# GECBalloonMCUFlightBoard_REV2_1_7-19-19.net
KiCad netlist of a schematic drawn in EAGLE
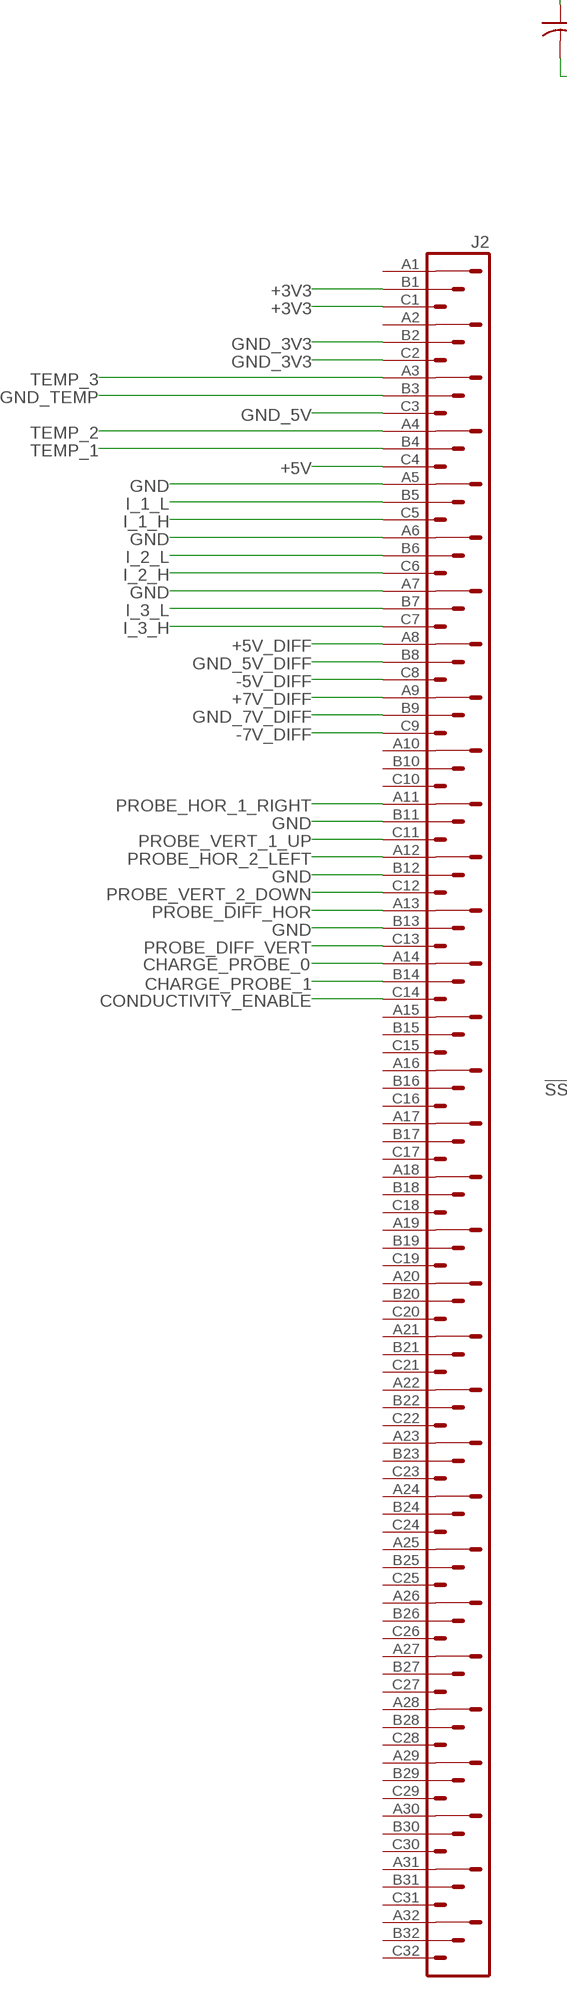
[diagram p0: schematic, sheet 1, part 1 of 2]
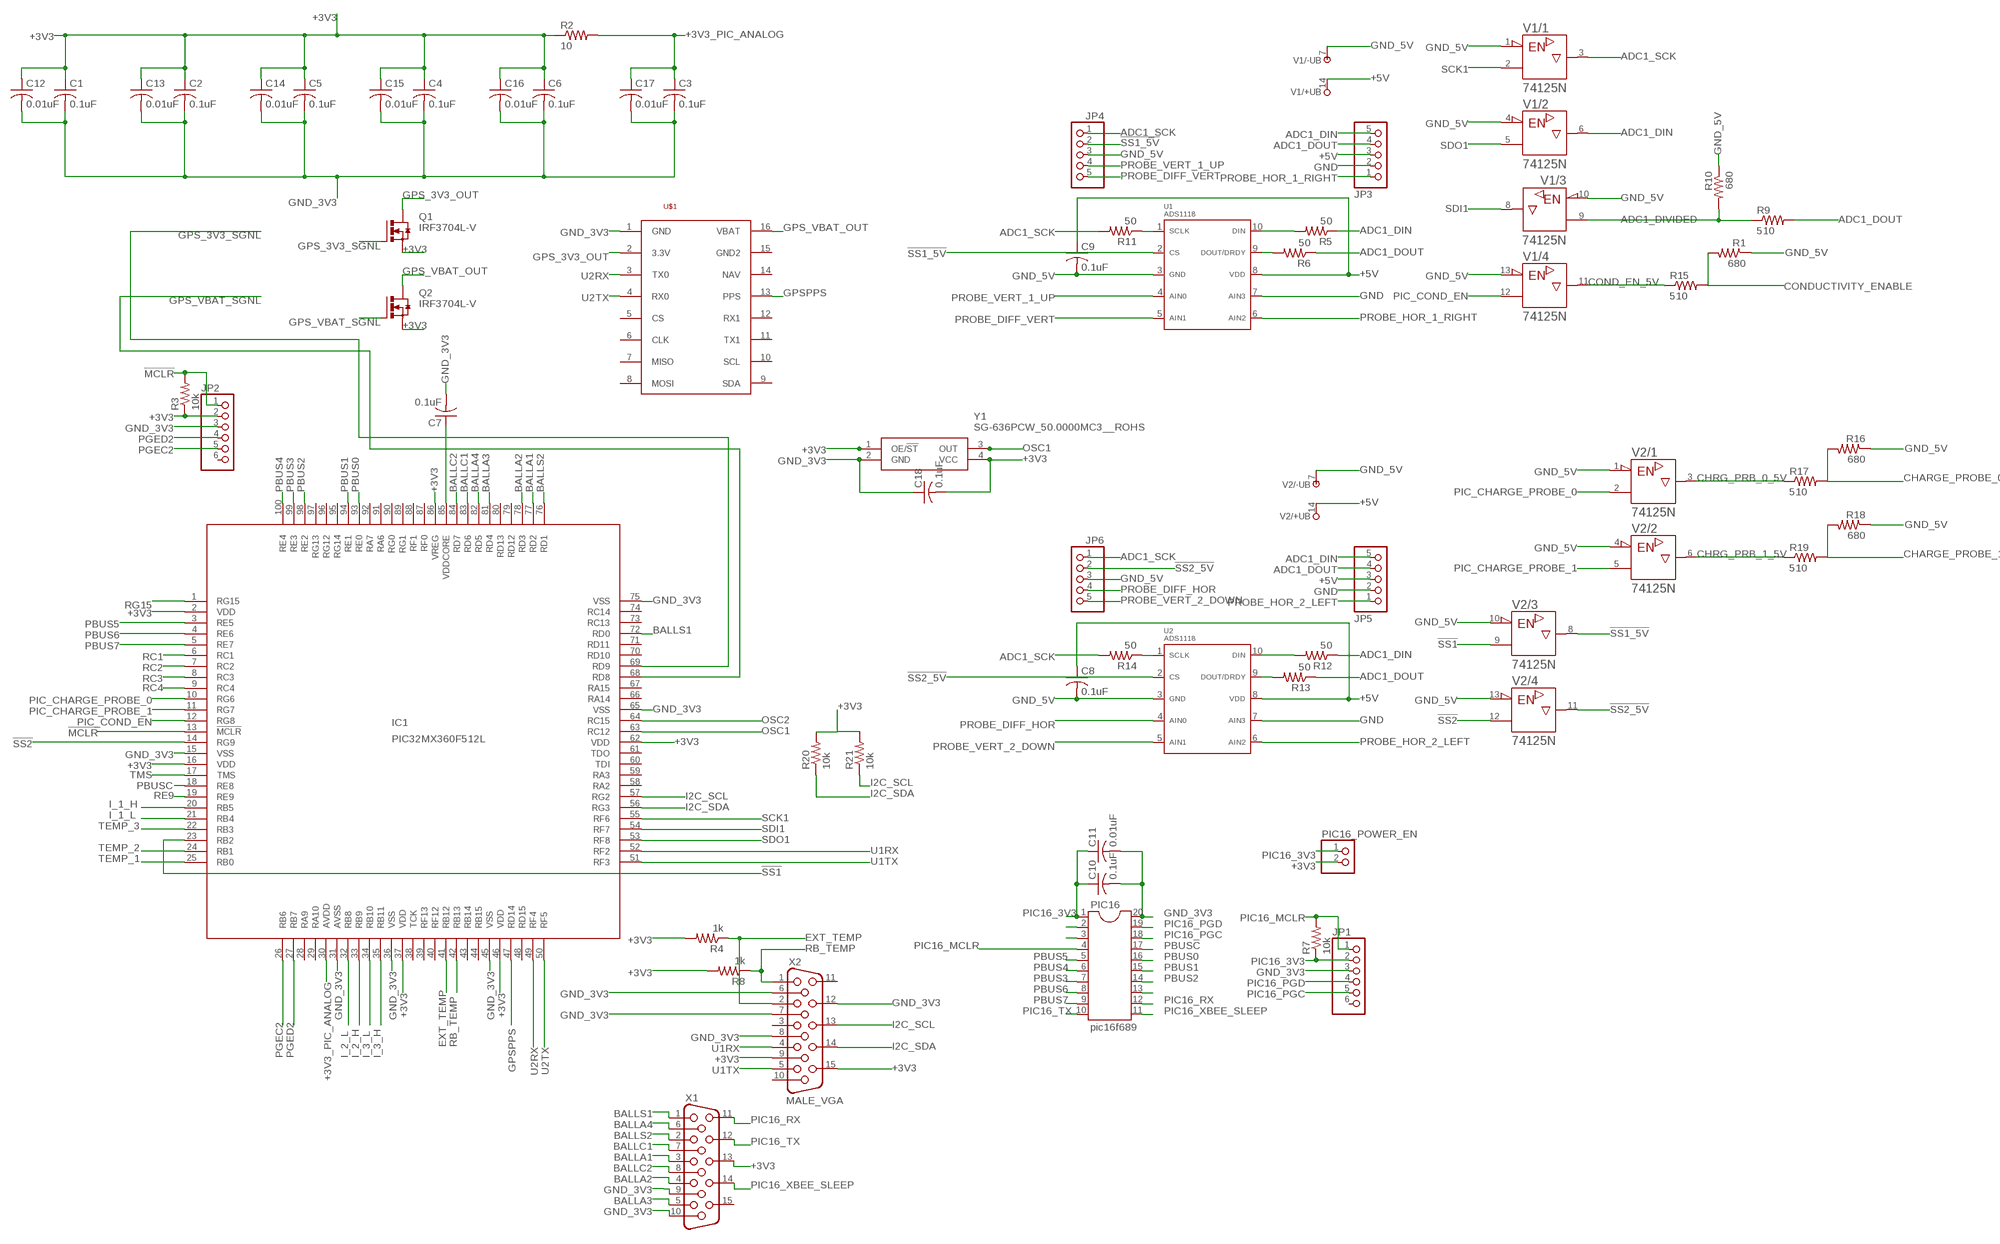
[diagram p1: schematic, sheet 1, part 2 of 2]

(export (version "E")
  (design (tool "Eeschema 10.0.6"))
  (components
    (comp (ref "C1")
      (value "0.1uF")
      (footprint "eagle-import:C1206")
      (libsource (lib "eagle-import") (part "C-USC1206"))
    )
    (comp (ref "C2")
      (value "0.1uF")
      (footprint "eagle-import:C1206")
      (libsource (lib "eagle-import") (part "C-USC1206"))
    )
    (comp (ref "C3")
      (value "0.1uF")
      (footprint "eagle-import:C1206")
      (libsource (lib "eagle-import") (part "C-USC1206"))
    )
    (comp (ref "C4")
      (value "0.1uF")
      (footprint "eagle-import:C1206")
      (libsource (lib "eagle-import") (part "C-USC1206"))
    )
    (comp (ref "C5")
      (value "0.1uF")
      (footprint "eagle-import:C1206")
      (libsource (lib "eagle-import") (part "C-USC1206"))
    )
    (comp (ref "C6")
      (value "0.1uF")
      (footprint "eagle-import:C1206")
      (libsource (lib "eagle-import") (part "C-USC1206"))
    )
    (comp (ref "C7")
      (value "0.1uF")
      (footprint "eagle-import:C1206")
      (libsource (lib "eagle-import") (part "C-USC1206"))
    )
    (comp (ref "C8")
      (value "0.1uF")
      (footprint "eagle-import:C1206")
      (libsource (lib "eagle-import") (part "C-USC1206"))
    )
    (comp (ref "C9")
      (value "0.1uF")
      (footprint "eagle-import:C1206")
      (libsource (lib "eagle-import") (part "C-USC1206"))
    )
    (comp (ref "C10")
      (value "0.1uF")
      (footprint "eagle-import:C1206")
      (libsource (lib "eagle-import") (part "C-USC1206"))
    )
    (comp (ref "C11")
      (value "0.01uF")
      (footprint "eagle-import:C1206")
      (libsource (lib "eagle-import") (part "C-USC1206"))
    )
    (comp (ref "C12")
      (value "0.01uF")
      (footprint "eagle-import:C1206")
      (libsource (lib "eagle-import") (part "C-USC1206"))
    )
    (comp (ref "C13")
      (value "0.01uF")
      (footprint "eagle-import:C1206")
      (libsource (lib "eagle-import") (part "C-USC1206"))
    )
    (comp (ref "C14")
      (value "0.01uF")
      (footprint "eagle-import:C1206")
      (libsource (lib "eagle-import") (part "C-USC1206"))
    )
    (comp (ref "C15")
      (value "0.01uF")
      (footprint "eagle-import:C1206")
      (libsource (lib "eagle-import") (part "C-USC1206"))
    )
    (comp (ref "C16")
      (value "0.01uF")
      (footprint "eagle-import:C1206")
      (libsource (lib "eagle-import") (part "C-USC1206"))
    )
    (comp (ref "C17")
      (value "0.01uF")
      (footprint "eagle-import:C1206")
      (libsource (lib "eagle-import") (part "C-USC1206"))
    )
    (comp (ref "C18")
      (value "0.1uF")
      (footprint "eagle-import:C1206")
      (libsource (lib "eagle-import") (part "C-USC1206"))
    )
    (comp (ref "IC1")
      (value "PIC32MX360F512L")
      (footprint "eagle-import:TQFP100")
      (libsource (lib "eagle-import") (part "PIC32MX360F512L"))
    )
    (comp (ref "J2")
      (value "VG96KB")
      (footprint "eagle-import:VG96KB")
      (libsource (lib "eagle-import") (part "VG96KB"))
    )
    (comp (ref "JP1")
      (value "PINHD-1X6")
      (footprint "eagle-import:1X06")
      (libsource (lib "eagle-import") (part "PINHD-1X6"))
    )
    (comp (ref "JP2")
      (value "PINHD-1X6")
      (footprint "eagle-import:1X06")
      (libsource (lib "eagle-import") (part "PINHD-1X6"))
    )
    (comp (ref "JP3")
      (value "PINHD-1X5")
      (footprint "eagle-import:1X05")
      (libsource (lib "eagle-import") (part "PINHD-1X5"))
    )
    (comp (ref "JP4")
      (value "PINHD-1X5")
      (footprint "eagle-import:1X05")
      (libsource (lib "eagle-import") (part "PINHD-1X5"))
    )
    (comp (ref "JP5")
      (value "PINHD-1X5")
      (footprint "eagle-import:1X05")
      (libsource (lib "eagle-import") (part "PINHD-1X5"))
    )
    (comp (ref "JP6")
      (value "PINHD-1X5")
      (footprint "eagle-import:1X05")
      (libsource (lib "eagle-import") (part "PINHD-1X5"))
    )
    (comp (ref "PIC16")
      (value "pic16f689")
      (footprint "eagle-import:DIL20")
      (libsource (lib "eagle-import") (part "DIL20"))
    )
    (comp (ref "PIC16_POWER_EN")
      (value "PINHD-1X2")
      (footprint "eagle-import:1X02")
      (libsource (lib "eagle-import") (part "PINHD-1X2"))
    )
    (comp (ref "Q1")
      (value "IRF3704L-V")
      (footprint "eagle-import:TO262-V")
      (libsource (lib "eagle-import") (part "IRF3704L-V"))
    )
    (comp (ref "Q2")
      (value "IRF3704L-V")
      (footprint "eagle-import:TO262-V")
      (libsource (lib "eagle-import") (part "IRF3704L-V"))
    )
    (comp (ref "R1")
      (value "680")
      (footprint "eagle-import:R1206")
      (libsource (lib "eagle-import") (part "resistor_R-US_R1206"))
    )
    (comp (ref "R2")
      (value "10")
      (footprint "eagle-import:M1206")
      (libsource (lib "eagle-import") (part "R-US_M1206"))
    )
    (comp (ref "R3")
      (value "10k")
      (footprint "eagle-import:M1206")
      (libsource (lib "eagle-import") (part "R-US_M1206"))
    )
    (comp (ref "R4")
      (value "1k")
      (footprint "eagle-import:0414_15")
      (libsource (lib "eagle-import") (part "resistor_R-US_0414/15"))
    )
    (comp (ref "R5")
      (value "50")
      (footprint "eagle-import:M1206")
      (libsource (lib "eagle-import") (part "R-US_M1206"))
    )
    (comp (ref "R6")
      (value "50")
      (footprint "eagle-import:M1206")
      (libsource (lib "eagle-import") (part "R-US_M1206"))
    )
    (comp (ref "R7")
      (value "10k")
      (footprint "eagle-import:M1206")
      (libsource (lib "eagle-import") (part "R-US_M1206"))
    )
    (comp (ref "R8")
      (value "1k")
      (footprint "eagle-import:0414_15")
      (libsource (lib "eagle-import") (part "resistor_R-US_0414/15"))
    )
    (comp (ref "R9")
      (value "510")
      (footprint "eagle-import:R1206")
      (libsource (lib "eagle-import") (part "resistor_R-US_R1206"))
    )
    (comp (ref "R10")
      (value "680")
      (footprint "eagle-import:R1206")
      (libsource (lib "eagle-import") (part "resistor_R-US_R1206"))
    )
    (comp (ref "R11")
      (value "50")
      (footprint "eagle-import:M1206")
      (libsource (lib "eagle-import") (part "R-US_M1206"))
    )
    (comp (ref "R12")
      (value "50")
      (footprint "eagle-import:M1206")
      (libsource (lib "eagle-import") (part "R-US_M1206"))
    )
    (comp (ref "R13")
      (value "50")
      (footprint "eagle-import:M1206")
      (libsource (lib "eagle-import") (part "R-US_M1206"))
    )
    (comp (ref "R14")
      (value "50")
      (footprint "eagle-import:M1206")
      (libsource (lib "eagle-import") (part "R-US_M1206"))
    )
    (comp (ref "R15")
      (value "510")
      (footprint "eagle-import:R1206")
      (libsource (lib "eagle-import") (part "resistor_R-US_R1206"))
    )
    (comp (ref "R16")
      (value "680")
      (footprint "eagle-import:R1206")
      (libsource (lib "eagle-import") (part "resistor_R-US_R1206"))
    )
    (comp (ref "R17")
      (value "510")
      (footprint "eagle-import:R1206")
      (libsource (lib "eagle-import") (part "resistor_R-US_R1206"))
    )
    (comp (ref "R18")
      (value "680")
      (footprint "eagle-import:R1206")
      (libsource (lib "eagle-import") (part "resistor_R-US_R1206"))
    )
    (comp (ref "R19")
      (value "510")
      (footprint "eagle-import:R1206")
      (libsource (lib "eagle-import") (part "resistor_R-US_R1206"))
    )
    (comp (ref "R20")
      (value "10k")
      (footprint "eagle-import:M1206")
      (libsource (lib "eagle-import") (part "R-US_M1206"))
    )
    (comp (ref "R21")
      (value "10k")
      (footprint "eagle-import:M1206")
      (libsource (lib "eagle-import") (part "R-US_M1206"))
    )
    (comp (ref "U$1")
      (value "SPARKFUN_VENUS_GPS_BREAKOUT")
      (footprint "eagle-import:SPARKFUN_BOARD")
      (libsource (lib "eagle-import") (part "SPARKFUN_VENUS_GPS_BREAKOUT"))
    )
    (comp (ref "U1")
      (value "ADS1118")
      (footprint "eagle-import:MSOP10")
      (libsource (lib "eagle-import") (part "ADS1118_MSOP10"))
    )
    (comp (ref "U2")
      (value "ADS1118")
      (footprint "eagle-import:MSOP10")
      (libsource (lib "eagle-import") (part "ADS1118_MSOP10"))
    )
    (comp (ref "V1")
      (value "74125N")
      (footprint "eagle-import:DIL14")
      (libsource (lib "eagle-import") (part "74125N"))
    )
    (comp (ref "V2")
      (value "74125N")
      (footprint "eagle-import:DIL14")
      (libsource (lib "eagle-import") (part "74125N"))
    )
    (comp (ref "X1")
      (value "HF15H")
      (footprint "eagle-import:HDF15H")
      (libsource (lib "eagle-import") (part "HF15H"))
    )
    (comp (ref "X2")
      (value "MALE_VGA")
      (footprint "eagle-import:MALE_PACKAGE")
      (libsource (lib "eagle-import") (part "MALE_VGA"))
    )
    (comp (ref "Y1")
      (value "SG-636PCW_50.0000MC3__ROHS")
      (footprint "eagle-import:SG-636")
      (fields (field (name "ARROW_PART_NUMBER") "SG-636PCW 50.0000MC3: ROHS"))
      (libsource (lib "eagle-import") (part "SG-636PCW_50.0000MC3__ROHS"))
    )
  )
  (nets
    (net (code "1") (name "/+3V3") (class "Default")
      (node (ref "C1") (pin "1") (pinfunction "1_1") (pintype "passive"))
      (node (ref "C12") (pin "1") (pinfunction "1_1") (pintype "passive"))
      (node (ref "C13") (pin "1") (pinfunction "1_1") (pintype "passive"))
      (node (ref "C14") (pin "1") (pinfunction "1_1") (pintype "passive"))
      (node (ref "C15") (pin "1") (pinfunction "1_1") (pintype "passive"))
      (node (ref "C16") (pin "1") (pinfunction "1_1") (pintype "passive"))
      (node (ref "C18") (pin "2") (pinfunction "2_2") (pintype "passive"))
      (node (ref "C2") (pin "1") (pinfunction "1_1") (pintype "passive"))
      (node (ref "C4") (pin "1") (pinfunction "1_1") (pintype "passive"))
      (node (ref "C5") (pin "1") (pinfunction "1_1") (pintype "passive"))
      (node (ref "C6") (pin "1") (pinfunction "1_1") (pintype "passive"))
      (node (ref "IC1") (pin "16") (pinfunction "VDD_16") (pintype "power_in"))
      (node (ref "IC1") (pin "2") (pinfunction "VDD_2") (pintype "power_in"))
      (node (ref "IC1") (pin "37") (pinfunction "VDD_37") (pintype "power_in"))
      (node (ref "IC1") (pin "46") (pinfunction "VDD_46") (pintype "power_in"))
      (node (ref "IC1") (pin "62") (pinfunction "VDD_62") (pintype "power_in"))
      (node (ref "IC1") (pin "86") (pinfunction "VREG_86") (pintype "passive"))
      (node (ref "J2") (pin "B1") (pinfunction "B1_B1") (pintype "passive"))
      (node (ref "J2") (pin "C1") (pinfunction "C1_C1") (pintype "passive"))
      (node (ref "JP2") (pin "2") (pinfunction "2_2") (pintype "passive"))
      (node (ref "PIC16_POWER_EN") (pin "2") (pinfunction "2_2") (pintype "passive"))
      (node (ref "Q1") (pin "3") (pinfunction "S_3") (pintype "passive"))
      (node (ref "Q2") (pin "3") (pinfunction "S_3") (pintype "passive"))
      (node (ref "R2") (pin "1") (pinfunction "1_1") (pintype "passive"))
      (node (ref "R20") (pin "2") (pinfunction "2_2") (pintype "passive"))
      (node (ref "R21") (pin "2") (pinfunction "2_2") (pintype "passive"))
      (node (ref "R3") (pin "1") (pinfunction "1_1") (pintype "passive"))
      (node (ref "R4") (pin "2") (pinfunction "2_2") (pintype "passive"))
      (node (ref "R8") (pin "2") (pinfunction "2_2") (pintype "passive"))
      (node (ref "X1") (pin "13") (pinfunction "13_13") (pintype "passive"))
      (node (ref "X2") (pin "15") (pinfunction "15_15") (pintype "passive"))
      (node (ref "X2") (pin "9") (pinfunction "9_9") (pintype "passive"))
      (node (ref "Y1") (pin "1") (pinfunction "OE/~{ST}_1") (pintype "input"))
      (node (ref "Y1") (pin "4") (pinfunction "VCC_4") (pintype "power_in"))
    )
    (net (code "2") (name "/+3V3_PIC_ANALOG") (class "Default")
      (node (ref "C17") (pin "1") (pinfunction "1_1") (pintype "passive"))
      (node (ref "C3") (pin "1") (pinfunction "1_1") (pintype "passive"))
      (node (ref "IC1") (pin "30") (pinfunction "AVDD_30") (pintype "power_in"))
      (node (ref "R2") (pin "2") (pinfunction "2_2") (pintype "passive"))
    )
    (net (code "3") (name "/+5V") (class "Default")
      (node (ref "C8") (pin "1") (pinfunction "1_1") (pintype "passive"))
      (node (ref "C9") (pin "1") (pinfunction "1_1") (pintype "passive"))
      (node (ref "J2") (pin "C4") (pinfunction "C4_C4") (pintype "passive"))
      (node (ref "JP3") (pin "3") (pinfunction "3_3") (pintype "passive"))
      (node (ref "JP5") (pin "3") (pinfunction "3_3") (pintype "passive"))
      (node (ref "U1") (pin "8") (pinfunction "VDD_8") (pintype "bidirectional"))
      (node (ref "U2") (pin "8") (pinfunction "VDD_8") (pintype "bidirectional"))
      (node (ref "V1") (pin "14") (pinfunction "+UB_14") (pintype "power_in"))
      (node (ref "V2") (pin "14") (pinfunction "+UB_14") (pintype "power_in"))
    )
    (net (code "4") (name "/+5V_DIFF") (class "Default")
      (node (ref "J2") (pin "A8") (pinfunction "A8_A8") (pintype "passive"))
    )
    (net (code "5") (name "/+7V_DIFF") (class "Default")
      (node (ref "J2") (pin "A9") (pinfunction "A9_A9") (pintype "passive"))
    )
    (net (code "6") (name "/-5V_DIFF") (class "Default")
      (node (ref "J2") (pin "C8") (pinfunction "C8_C8") (pintype "passive"))
    )
    (net (code "7") (name "/-7V_DIFF") (class "Default")
      (node (ref "J2") (pin "C9") (pinfunction "C9_C9") (pintype "passive"))
    )
    (net (code "8") (name "/ADC1_DIN") (class "Default")
      (node (ref "JP3") (pin "5") (pinfunction "5_5") (pintype "passive"))
      (node (ref "JP5") (pin "5") (pinfunction "5_5") (pintype "passive"))
      (node (ref "R12") (pin "1") (pinfunction "1_1") (pintype "passive"))
      (node (ref "R5") (pin "1") (pinfunction "1_1") (pintype "passive"))
      (node (ref "V1") (pin "6") (pinfunction "Y_6") (pintype "tri_state"))
    )
    (net (code "9") (name "/ADC1_DIVIDED") (class "Default")
      (node (ref "R10") (pin "2") (pinfunction "2_2") (pintype "passive"))
      (node (ref "R9") (pin "1") (pinfunction "1_1") (pintype "passive"))
      (node (ref "V1") (pin "9") (pinfunction "A_9") (pintype "input"))
    )
    (net (code "10") (name "/ADC1_DOUT") (class "Default")
      (node (ref "JP3") (pin "4") (pinfunction "4_4") (pintype "passive"))
      (node (ref "JP5") (pin "4") (pinfunction "4_4") (pintype "passive"))
      (node (ref "R13") (pin "1") (pinfunction "1_1") (pintype "passive"))
      (node (ref "R6") (pin "1") (pinfunction "1_1") (pintype "passive"))
      (node (ref "R9") (pin "2") (pinfunction "2_2") (pintype "passive"))
    )
    (net (code "11") (name "/ADC1_SCK") (class "Default")
      (node (ref "JP4") (pin "1") (pinfunction "1_1") (pintype "passive"))
      (node (ref "JP6") (pin "1") (pinfunction "1_1") (pintype "passive"))
      (node (ref "R11") (pin "2") (pinfunction "2_2") (pintype "passive"))
      (node (ref "R14") (pin "2") (pinfunction "2_2") (pintype "passive"))
      (node (ref "V1") (pin "3") (pinfunction "Y_3") (pintype "tri_state"))
    )
    (net (code "12") (name "/BALLA1") (class "Default")
      (node (ref "IC1") (pin "77") (pinfunction "RD2_77") (pintype "bidirectional"))
      (node (ref "X1") (pin "3") (pinfunction "3_3") (pintype "passive"))
    )
    (net (code "13") (name "/BALLA2") (class "Default")
      (node (ref "IC1") (pin "78") (pinfunction "RD3_78") (pintype "bidirectional"))
      (node (ref "X1") (pin "4") (pinfunction "4_4") (pintype "passive"))
    )
    (net (code "14") (name "/BALLA3") (class "Default")
      (node (ref "IC1") (pin "81") (pinfunction "RD4_81") (pintype "bidirectional"))
      (node (ref "X1") (pin "5") (pinfunction "5_5") (pintype "passive"))
    )
    (net (code "15") (name "/BALLA4") (class "Default")
      (node (ref "IC1") (pin "82") (pinfunction "RD5_82") (pintype "bidirectional"))
      (node (ref "X1") (pin "6") (pinfunction "6_6") (pintype "passive"))
    )
    (net (code "16") (name "/BALLC1") (class "Default")
      (node (ref "IC1") (pin "83") (pinfunction "RD6_83") (pintype "bidirectional"))
      (node (ref "X1") (pin "7") (pinfunction "7_7") (pintype "passive"))
    )
    (net (code "17") (name "/BALLC2") (class "Default")
      (node (ref "IC1") (pin "84") (pinfunction "RD7_84") (pintype "bidirectional"))
      (node (ref "X1") (pin "8") (pinfunction "8_8") (pintype "passive"))
    )
    (net (code "18") (name "/BALLS1") (class "Default")
      (node (ref "IC1") (pin "72") (pinfunction "RD0_72") (pintype "bidirectional"))
      (node (ref "X1") (pin "1") (pinfunction "1_1") (pintype "passive"))
    )
    (net (code "19") (name "/BALLS2") (class "Default")
      (node (ref "IC1") (pin "76") (pinfunction "RD1_76") (pintype "bidirectional"))
      (node (ref "X1") (pin "2") (pinfunction "2_2") (pintype "passive"))
    )
    (net (code "20") (name "/CHARGE_PROBE_0") (class "Default")
      (node (ref "J2") (pin "A14") (pinfunction "A14_A14") (pintype "passive"))
      (node (ref "R16") (pin "2") (pinfunction "2_2") (pintype "passive"))
      (node (ref "R17") (pin "2") (pinfunction "2_2") (pintype "passive"))
    )
    (net (code "21") (name "/CHARGE_PROBE_1") (class "Default")
      (node (ref "J2") (pin "B14") (pinfunction "B14_B14") (pintype "passive"))
      (node (ref "R18") (pin "2") (pinfunction "2_2") (pintype "passive"))
      (node (ref "R19") (pin "2") (pinfunction "2_2") (pintype "passive"))
    )
    (net (code "22") (name "/CHRG_PRB_0_5V") (class "Default")
      (node (ref "R17") (pin "1") (pinfunction "1_1") (pintype "passive"))
      (node (ref "V2") (pin "3") (pinfunction "Y_3") (pintype "tri_state"))
    )
    (net (code "23") (name "/CHRG_PRB_1_5V") (class "Default")
      (node (ref "R19") (pin "1") (pinfunction "1_1") (pintype "passive"))
      (node (ref "V2") (pin "6") (pinfunction "Y_6") (pintype "tri_state"))
    )
    (net (code "24") (name "/CONDUCTIVITY_ENABLE") (class "Default")
      (node (ref "J2") (pin "C14") (pinfunction "C14_C14") (pintype "passive"))
      (node (ref "R1") (pin "2") (pinfunction "2_2") (pintype "passive"))
      (node (ref "R15") (pin "2") (pinfunction "2_2") (pintype "passive"))
    )
    (net (code "25") (name "/COND_EN_5V") (class "Default")
      (node (ref "R15") (pin "1") (pinfunction "1_1") (pintype "passive"))
      (node (ref "V1") (pin "11") (pinfunction "Y_11") (pintype "tri_state"))
    )
    (net (code "26") (name "/EXT_TEMP") (class "Default")
      (node (ref "IC1") (pin "41") (pinfunction "RB12_41") (pintype "bidirectional"))
      (node (ref "R4") (pin "1") (pinfunction "1_1") (pintype "passive"))
      (node (ref "X2") (pin "2") (pinfunction "2_2") (pintype "passive"))
    )
    (net (code "27") (name "/GND") (class "Default")
      (node (ref "J2") (pin "A5") (pinfunction "A5_A5") (pintype "passive"))
      (node (ref "J2") (pin "A6") (pinfunction "A6_A6") (pintype "passive"))
      (node (ref "J2") (pin "A7") (pinfunction "A7_A7") (pintype "passive"))
      (node (ref "J2") (pin "B11") (pinfunction "B11_B11") (pintype "passive"))
      (node (ref "J2") (pin "B12") (pinfunction "B12_B12") (pintype "passive"))
      (node (ref "J2") (pin "B13") (pinfunction "B13_B13") (pintype "passive"))
      (node (ref "JP3") (pin "2") (pinfunction "2_2") (pintype "passive"))
      (node (ref "JP5") (pin "2") (pinfunction "2_2") (pintype "passive"))
      (node (ref "U1") (pin "7") (pinfunction "AIN3_7") (pintype "bidirectional"))
      (node (ref "U2") (pin "7") (pinfunction "AIN3_7") (pintype "bidirectional"))
    )
    (net (code "28") (name "/GND_3V3") (class "Default")
      (node (ref "C1") (pin "2") (pinfunction "2_2") (pintype "passive"))
      (node (ref "C10") (pin "2") (pinfunction "2_2") (pintype "passive"))
      (node (ref "C11") (pin "2") (pinfunction "2_2") (pintype "passive"))
      (node (ref "C12") (pin "2") (pinfunction "2_2") (pintype "passive"))
      (node (ref "C13") (pin "2") (pinfunction "2_2") (pintype "passive"))
      (node (ref "C14") (pin "2") (pinfunction "2_2") (pintype "passive"))
      (node (ref "C15") (pin "2") (pinfunction "2_2") (pintype "passive"))
      (node (ref "C16") (pin "2") (pinfunction "2_2") (pintype "passive"))
      (node (ref "C17") (pin "2") (pinfunction "2_2") (pintype "passive"))
      (node (ref "C18") (pin "1") (pinfunction "1_1") (pintype "passive"))
      (node (ref "C2") (pin "2") (pinfunction "2_2") (pintype "passive"))
      (node (ref "C3") (pin "2") (pinfunction "2_2") (pintype "passive"))
      (node (ref "C4") (pin "2") (pinfunction "2_2") (pintype "passive"))
      (node (ref "C5") (pin "2") (pinfunction "2_2") (pintype "passive"))
      (node (ref "C6") (pin "2") (pinfunction "2_2") (pintype "passive"))
      (node (ref "C7") (pin "2") (pinfunction "2_2") (pintype "passive"))
      (node (ref "IC1") (pin "15") (pinfunction "VSS_15") (pintype "power_in"))
      (node (ref "IC1") (pin "31") (pinfunction "AVSS_31") (pintype "power_in"))
      (node (ref "IC1") (pin "36") (pinfunction "VSS_36") (pintype "power_in"))
      (node (ref "IC1") (pin "45") (pinfunction "VSS_45") (pintype "power_in"))
      (node (ref "IC1") (pin "65") (pinfunction "VSS_65") (pintype "power_in"))
      (node (ref "IC1") (pin "75") (pinfunction "VSS_75") (pintype "power_in"))
      (node (ref "J2") (pin "B2") (pinfunction "B2_B2") (pintype "passive"))
      (node (ref "J2") (pin "C2") (pinfunction "C2_C2") (pintype "passive"))
      (node (ref "JP1") (pin "3") (pinfunction "3_3") (pintype "passive"))
      (node (ref "JP2") (pin "3") (pinfunction "3_3") (pintype "passive"))
      (node (ref "PIC16") (pin "20") (pinfunction "20_20") (pintype "passive"))
      (node (ref "U$1") (pin "1") (pinfunction "GND_1") (pintype "bidirectional"))
      (node (ref "X1") (pin "10") (pinfunction "10_10") (pintype "passive"))
      (node (ref "X1") (pin "9") (pinfunction "9_9") (pintype "passive"))
      (node (ref "X2") (pin "12") (pinfunction "12_12") (pintype "passive"))
      (node (ref "X2") (pin "6") (pinfunction "6_6") (pintype "passive"))
      (node (ref "X2") (pin "7") (pinfunction "7_7") (pintype "passive"))
      (node (ref "X2") (pin "8") (pinfunction "8_8") (pintype "passive"))
      (node (ref "Y1") (pin "2") (pinfunction "GND_2") (pintype "power_in"))
    )
    (net (code "29") (name "/GND_5V") (class "Default")
      (node (ref "C8") (pin "2") (pinfunction "2_2") (pintype "passive"))
      (node (ref "C9") (pin "2") (pinfunction "2_2") (pintype "passive"))
      (node (ref "J2") (pin "C3") (pinfunction "C3_C3") (pintype "passive"))
      (node (ref "JP4") (pin "3") (pinfunction "3_3") (pintype "passive"))
      (node (ref "JP6") (pin "3") (pinfunction "3_3") (pintype "passive"))
      (node (ref "R1") (pin "1") (pinfunction "1_1") (pintype "passive"))
      (node (ref "R10") (pin "1") (pinfunction "1_1") (pintype "passive"))
      (node (ref "R16") (pin "1") (pinfunction "1_1") (pintype "passive"))
      (node (ref "R18") (pin "1") (pinfunction "1_1") (pintype "passive"))
      (node (ref "U1") (pin "3") (pinfunction "GND_3") (pintype "bidirectional"))
      (node (ref "U2") (pin "3") (pinfunction "GND_3") (pintype "bidirectional"))
      (node (ref "V1") (pin "1") (pinfunction "~{G}_1") (pintype "input"))
      (node (ref "V1") (pin "10") (pinfunction "~{G}_10") (pintype "input"))
      (node (ref "V1") (pin "13") (pinfunction "~{G}_13") (pintype "input"))
      (node (ref "V1") (pin "4") (pinfunction "~{G}_4") (pintype "input"))
      (node (ref "V1") (pin "7") (pinfunction "-UB_7") (pintype "power_in"))
      (node (ref "V2") (pin "1") (pinfunction "~{G}_1") (pintype "input"))
      (node (ref "V2") (pin "10") (pinfunction "~{G}_10") (pintype "input"))
      (node (ref "V2") (pin "13") (pinfunction "~{G}_13") (pintype "input"))
      (node (ref "V2") (pin "4") (pinfunction "~{G}_4") (pintype "input"))
      (node (ref "V2") (pin "7") (pinfunction "-UB_7") (pintype "power_in"))
    )
    (net (code "30") (name "/GND_5V_DIFF") (class "Default")
      (node (ref "J2") (pin "B8") (pinfunction "B8_B8") (pintype "passive"))
    )
    (net (code "31") (name "/GND_7V_DIFF") (class "Default")
      (node (ref "J2") (pin "B9") (pinfunction "B9_B9") (pintype "passive"))
    )
    (net (code "32") (name "/GND_TEMP") (class "Default")
      (node (ref "J2") (pin "B3") (pinfunction "B3_B3") (pintype "passive"))
    )
    (net (code "33") (name "/GPSPPS") (class "Default")
      (node (ref "IC1") (pin "47") (pinfunction "RD14_47") (pintype "bidirectional"))
      (node (ref "U$1") (pin "13") (pinfunction "PPS_13") (pintype "bidirectional"))
    )
    (net (code "34") (name "/GPS_3V3_OUT") (class "Default")
      (node (ref "Q1") (pin "2") (pinfunction "D_2") (pintype "passive"))
      (node (ref "U$1") (pin "2") (pinfunction "3.3V_2") (pintype "bidirectional"))
    )
    (net (code "35") (name "/GPS_3V3_SGNL") (class "Default")
      (node (ref "IC1") (pin "69") (pinfunction "RD9_69") (pintype "bidirectional"))
      (node (ref "Q1") (pin "1") (pinfunction "G_1") (pintype "passive"))
    )
    (net (code "36") (name "/GPS_VBAT_OUT") (class "Default")
      (node (ref "Q2") (pin "2") (pinfunction "D_2") (pintype "passive"))
      (node (ref "U$1") (pin "16") (pinfunction "VBAT_16") (pintype "bidirectional"))
    )
    (net (code "37") (name "/GPS_VBAT_SGNL") (class "Default")
      (node (ref "IC1") (pin "68") (pinfunction "RD8_68") (pintype "bidirectional"))
      (node (ref "Q2") (pin "1") (pinfunction "G_1") (pintype "passive"))
    )
    (net (code "38") (name "/I2C_SCL") (class "Default")
      (node (ref "IC1") (pin "57") (pinfunction "RG2_57") (pintype "bidirectional"))
      (node (ref "R21") (pin "1") (pinfunction "1_1") (pintype "passive"))
      (node (ref "X2") (pin "13") (pinfunction "13_13") (pintype "passive"))
    )
    (net (code "39") (name "/I2C_SDA") (class "Default")
      (node (ref "IC1") (pin "56") (pinfunction "RG3_56") (pintype "bidirectional"))
      (node (ref "R20") (pin "1") (pinfunction "1_1") (pintype "passive"))
      (node (ref "X2") (pin "14") (pinfunction "14_14") (pintype "passive"))
    )
    (net (code "40") (name "/I_1_H") (class "Default")
      (node (ref "IC1") (pin "20") (pinfunction "RB5_20") (pintype "bidirectional"))
      (node (ref "J2") (pin "C5") (pinfunction "C5_C5") (pintype "passive"))
    )
    (net (code "41") (name "/I_1_L") (class "Default")
      (node (ref "IC1") (pin "21") (pinfunction "RB4_21") (pintype "bidirectional"))
      (node (ref "J2") (pin "B5") (pinfunction "B5_B5") (pintype "passive"))
    )
    (net (code "42") (name "/I_2_H") (class "Default")
      (node (ref "IC1") (pin "33") (pinfunction "RB9_33") (pintype "bidirectional"))
      (node (ref "J2") (pin "C6") (pinfunction "C6_C6") (pintype "passive"))
    )
    (net (code "43") (name "/I_2_L") (class "Default")
      (node (ref "IC1") (pin "32") (pinfunction "RB8_32") (pintype "bidirectional"))
      (node (ref "J2") (pin "B6") (pinfunction "B6_B6") (pintype "passive"))
    )
    (net (code "44") (name "/I_3_H") (class "Default")
      (node (ref "IC1") (pin "35") (pinfunction "RB11_35") (pintype "bidirectional"))
      (node (ref "J2") (pin "C7") (pinfunction "C7_C7") (pintype "passive"))
    )
    (net (code "45") (name "/I_3_L") (class "Default")
      (node (ref "IC1") (pin "34") (pinfunction "RB10_34") (pintype "bidirectional"))
      (node (ref "J2") (pin "B7") (pinfunction "B7_B7") (pintype "passive"))
    )
    (net (code "46") (name "/OSC1") (class "Default")
      (node (ref "IC1") (pin "63") (pinfunction "RC12_63") (pintype "bidirectional"))
      (node (ref "Y1") (pin "3") (pinfunction "OUT_3") (pintype "output"))
    )
    (net (code "47") (name "/OSC2") (class "Default")
      (node (ref "IC1") (pin "64") (pinfunction "RC15_64") (pintype "bidirectional"))
    )
    (net (code "48") (name "/PBUS0") (class "Default")
      (node (ref "IC1") (pin "93") (pinfunction "RE0_93") (pintype "bidirectional"))
      (node (ref "PIC16") (pin "16") (pinfunction "16_16") (pintype "passive"))
    )
    (net (code "49") (name "/PBUS1") (class "Default")
      (node (ref "IC1") (pin "94") (pinfunction "RE1_94") (pintype "bidirectional"))
      (node (ref "PIC16") (pin "15") (pinfunction "15_15") (pintype "passive"))
    )
    (net (code "50") (name "/PBUS2") (class "Default")
      (node (ref "IC1") (pin "98") (pinfunction "RE2_98") (pintype "bidirectional"))
      (node (ref "PIC16") (pin "14") (pinfunction "14_14") (pintype "passive"))
    )
    (net (code "51") (name "/PBUS3") (class "Default")
      (node (ref "IC1") (pin "99") (pinfunction "RE3_99") (pintype "bidirectional"))
      (node (ref "PIC16") (pin "7") (pinfunction "7_7") (pintype "passive"))
    )
    (net (code "52") (name "/PBUS4") (class "Default")
      (node (ref "IC1") (pin "100") (pinfunction "RE4_100") (pintype "bidirectional"))
      (node (ref "PIC16") (pin "6") (pinfunction "6_6") (pintype "passive"))
    )
    (net (code "53") (name "/PBUS5") (class "Default")
      (node (ref "IC1") (pin "3") (pinfunction "RE5_3") (pintype "bidirectional"))
      (node (ref "PIC16") (pin "5") (pinfunction "5_5") (pintype "passive"))
    )
    (net (code "54") (name "/PBUS6") (class "Default")
      (node (ref "IC1") (pin "4") (pinfunction "RE6_4") (pintype "bidirectional"))
      (node (ref "PIC16") (pin "8") (pinfunction "8_8") (pintype "passive"))
    )
    (net (code "55") (name "/PBUS7") (class "Default")
      (node (ref "IC1") (pin "5") (pinfunction "RE7_5") (pintype "bidirectional"))
      (node (ref "PIC16") (pin "9") (pinfunction "9_9") (pintype "passive"))
    )
    (net (code "56") (name "/PBUSC") (class "Default")
      (node (ref "IC1") (pin "18") (pinfunction "RE8_18") (pintype "bidirectional"))
      (node (ref "PIC16") (pin "17") (pinfunction "17_17") (pintype "passive"))
    )
    (net (code "57") (name "/PGEC2") (class "Default")
      (node (ref "IC1") (pin "26") (pinfunction "RB6_26") (pintype "bidirectional"))
      (node (ref "JP2") (pin "5") (pinfunction "5_5") (pintype "passive"))
    )
    (net (code "58") (name "/PGED2") (class "Default")
      (node (ref "IC1") (pin "27") (pinfunction "RB7_27") (pintype "bidirectional"))
      (node (ref "JP2") (pin "4") (pinfunction "4_4") (pintype "passive"))
    )
    (net (code "59") (name "/PIC16_3V3") (class "Default")
      (node (ref "C10") (pin "1") (pinfunction "1_1") (pintype "passive"))
      (node (ref "C11") (pin "1") (pinfunction "1_1") (pintype "passive"))
      (node (ref "JP1") (pin "2") (pinfunction "2_2") (pintype "passive"))
      (node (ref "PIC16") (pin "1") (pinfunction "1_1") (pintype "passive"))
      (node (ref "PIC16_POWER_EN") (pin "1") (pinfunction "1_1") (pintype "passive"))
      (node (ref "R7") (pin "1") (pinfunction "1_1") (pintype "passive"))
    )
    (net (code "60") (name "/PIC16_MCLR") (class "Default")
      (node (ref "JP1") (pin "1") (pinfunction "1_1") (pintype "passive"))
      (node (ref "PIC16") (pin "4") (pinfunction "4_4") (pintype "passive"))
      (node (ref "R7") (pin "2") (pinfunction "2_2") (pintype "passive"))
    )
    (net (code "61") (name "/PIC16_PGC") (class "Default")
      (node (ref "JP1") (pin "5") (pinfunction "5_5") (pintype "passive"))
      (node (ref "PIC16") (pin "18") (pinfunction "18_18") (pintype "passive"))
    )
    (net (code "62") (name "/PIC16_PGD") (class "Default")
      (node (ref "JP1") (pin "4") (pinfunction "4_4") (pintype "passive"))
      (node (ref "PIC16") (pin "19") (pinfunction "19_19") (pintype "passive"))
    )
    (net (code "63") (name "/PIC16_RX") (class "Default")
      (node (ref "PIC16") (pin "12") (pinfunction "12_12") (pintype "passive"))
      (node (ref "X1") (pin "11") (pinfunction "11_11") (pintype "passive"))
    )
    (net (code "64") (name "/PIC16_TX") (class "Default")
      (node (ref "PIC16") (pin "10") (pinfunction "10_10") (pintype "passive"))
      (node (ref "X1") (pin "12") (pinfunction "12_12") (pintype "passive"))
    )
    (net (code "65") (name "/PIC16_XBEE_SLEEP") (class "Default")
      (node (ref "PIC16") (pin "11") (pinfunction "11_11") (pintype "passive"))
      (node (ref "X1") (pin "14") (pinfunction "14_14") (pintype "passive"))
    )
    (net (code "66") (name "/PIC_CHARGE_PROBE_0") (class "Default")
      (node (ref "IC1") (pin "10") (pinfunction "RG6_10") (pintype "bidirectional"))
      (node (ref "V2") (pin "2") (pinfunction "A_2") (pintype "input"))
    )
    (net (code "67") (name "/PIC_CHARGE_PROBE_1") (class "Default")
      (node (ref "IC1") (pin "11") (pinfunction "RG7_11") (pintype "bidirectional"))
      (node (ref "V2") (pin "5") (pinfunction "A_5") (pintype "input"))
    )
    (net (code "68") (name "/PIC_COND_EN") (class "Default")
      (node (ref "IC1") (pin "12") (pinfunction "RG8_12") (pintype "bidirectional"))
      (node (ref "V1") (pin "12") (pinfunction "A_12") (pintype "input"))
    )
    (net (code "69") (name "/PROBE_DIFF_HOR") (class "Default")
      (node (ref "J2") (pin "A13") (pinfunction "A13_A13") (pintype "passive"))
      (node (ref "JP6") (pin "4") (pinfunction "4_4") (pintype "passive"))
      (node (ref "U2") (pin "4") (pinfunction "AIN0_4") (pintype "bidirectional"))
    )
    (net (code "70") (name "/PROBE_DIFF_VERT") (class "Default")
      (node (ref "J2") (pin "C13") (pinfunction "C13_C13") (pintype "passive"))
      (node (ref "JP4") (pin "5") (pinfunction "5_5") (pintype "passive"))
      (node (ref "U1") (pin "5") (pinfunction "AIN1_5") (pintype "bidirectional"))
    )
    (net (code "71") (name "/PROBE_HOR_1_RIGHT") (class "Default")
      (node (ref "J2") (pin "A11") (pinfunction "A11_A11") (pintype "passive"))
      (node (ref "JP3") (pin "1") (pinfunction "1_1") (pintype "passive"))
      (node (ref "U1") (pin "6") (pinfunction "AIN2_6") (pintype "bidirectional"))
    )
    (net (code "72") (name "/PROBE_HOR_2_LEFT") (class "Default")
      (node (ref "J2") (pin "A12") (pinfunction "A12_A12") (pintype "passive"))
      (node (ref "JP5") (pin "1") (pinfunction "1_1") (pintype "passive"))
      (node (ref "U2") (pin "6") (pinfunction "AIN2_6") (pintype "bidirectional"))
    )
    (net (code "73") (name "/PROBE_VERT_1_UP") (class "Default")
      (node (ref "J2") (pin "C11") (pinfunction "C11_C11") (pintype "passive"))
      (node (ref "JP4") (pin "4") (pinfunction "4_4") (pintype "passive"))
      (node (ref "U1") (pin "4") (pinfunction "AIN0_4") (pintype "bidirectional"))
    )
    (net (code "74") (name "/PROBE_VERT_2_DOWN") (class "Default")
      (node (ref "J2") (pin "C12") (pinfunction "C12_C12") (pintype "passive"))
      (node (ref "JP6") (pin "5") (pinfunction "5_5") (pintype "passive"))
      (node (ref "U2") (pin "5") (pinfunction "AIN1_5") (pintype "bidirectional"))
    )
    (net (code "75") (name "/RB_TEMP") (class "Default")
      (node (ref "IC1") (pin "42") (pinfunction "RB13_42") (pintype "bidirectional"))
      (node (ref "R8") (pin "1") (pinfunction "1_1") (pintype "passive"))
      (node (ref "X2") (pin "1") (pinfunction "1_1") (pintype "passive"))
    )
    (net (code "76") (name "/RC1") (class "Default")
      (node (ref "IC1") (pin "6") (pinfunction "RC1_6") (pintype "bidirectional"))
    )
    (net (code "77") (name "/RC2") (class "Default")
      (node (ref "IC1") (pin "7") (pinfunction "RC2_7") (pintype "bidirectional"))
    )
    (net (code "78") (name "/RC3") (class "Default")
      (node (ref "IC1") (pin "8") (pinfunction "RC3_8") (pintype "bidirectional"))
    )
    (net (code "79") (name "/RC4") (class "Default")
      (node (ref "IC1") (pin "9") (pinfunction "RC4_9") (pintype "bidirectional"))
    )
    (net (code "80") (name "/RE9") (class "Default")
      (node (ref "IC1") (pin "19") (pinfunction "RE9_19") (pintype "bidirectional"))
    )
    (net (code "81") (name "/RG15") (class "Default")
      (node (ref "IC1") (pin "1") (pinfunction "RG15_1") (pintype "bidirectional"))
    )
    (net (code "82") (name "/SCK1") (class "Default")
      (node (ref "IC1") (pin "55") (pinfunction "RF6_55") (pintype "bidirectional"))
      (node (ref "V1") (pin "2") (pinfunction "A_2") (pintype "input"))
    )
    (net (code "83") (name "/SDI1") (class "Default")
      (node (ref "IC1") (pin "54") (pinfunction "RF7_54") (pintype "bidirectional"))
      (node (ref "V1") (pin "8") (pinfunction "Y_8") (pintype "tri_state"))
    )
    (net (code "84") (name "/SDO1") (class "Default")
      (node (ref "IC1") (pin "53") (pinfunction "RF8_53") (pintype "bidirectional"))
      (node (ref "V1") (pin "5") (pinfunction "A_5") (pintype "input"))
    )
    (net (code "85") (name "/TEMP_1") (class "Default")
      (node (ref "IC1") (pin "25") (pinfunction "RB0_25") (pintype "bidirectional"))
      (node (ref "J2") (pin "B4") (pinfunction "B4_B4") (pintype "passive"))
    )
    (net (code "86") (name "/TEMP_2") (class "Default")
      (node (ref "IC1") (pin "24") (pinfunction "RB1_24") (pintype "bidirectional"))
      (node (ref "J2") (pin "A4") (pinfunction "A4_A4") (pintype "passive"))
    )
    (net (code "87") (name "/TEMP_3") (class "Default")
      (node (ref "IC1") (pin "22") (pinfunction "RB3_22") (pintype "bidirectional"))
      (node (ref "J2") (pin "A3") (pinfunction "A3_A3") (pintype "passive"))
    )
    (net (code "88") (name "/TMS") (class "Default")
      (node (ref "IC1") (pin "17") (pinfunction "TMS_17") (pintype "input"))
    )
    (net (code "89") (name "/U1RX") (class "Default")
      (node (ref "IC1") (pin "52") (pinfunction "RF2_52") (pintype "bidirectional"))
      (node (ref "X2") (pin "4") (pinfunction "4_4") (pintype "passive"))
    )
    (net (code "90") (name "/U1TX") (class "Default")
      (node (ref "IC1") (pin "51") (pinfunction "RF3_51") (pintype "bidirectional"))
      (node (ref "X2") (pin "5") (pinfunction "5_5") (pintype "passive"))
    )
    (net (code "91") (name "/U2RX") (class "Default")
      (node (ref "IC1") (pin "49") (pinfunction "RF4_49") (pintype "bidirectional"))
      (node (ref "U$1") (pin "3") (pinfunction "TX0_3") (pintype "bidirectional"))
    )
    (net (code "92") (name "/U2TX") (class "Default")
      (node (ref "IC1") (pin "50") (pinfunction "RF5_50") (pintype "bidirectional"))
      (node (ref "U$1") (pin "4") (pinfunction "RX0_4") (pintype "bidirectional"))
    )
    (net (code "93") (name "/~{MCLR}") (class "Default")
      (node (ref "IC1") (pin "13") (pinfunction "~{MCLR}_13") (pintype "input"))
      (node (ref "JP2") (pin "1") (pinfunction "1_1") (pintype "passive"))
      (node (ref "R3") (pin "2") (pinfunction "2_2") (pintype "passive"))
    )
    (net (code "94") (name "/~{SS1_5V}") (class "Default")
      (node (ref "JP4") (pin "2") (pinfunction "2_2") (pintype "passive"))
      (node (ref "U1") (pin "2") (pinfunction "CS_2") (pintype "bidirectional"))
      (node (ref "V2") (pin "8") (pinfunction "Y_8") (pintype "tri_state"))
    )
    (net (code "95") (name "/~{SS1}") (class "Default")
      (node (ref "IC1") (pin "23") (pinfunction "RB2_23") (pintype "bidirectional"))
      (node (ref "V2") (pin "9") (pinfunction "A_9") (pintype "input"))
    )
    (net (code "96") (name "/~{SS2_5V}") (class "Default")
      (node (ref "JP6") (pin "2") (pinfunction "2_2") (pintype "passive"))
      (node (ref "U2") (pin "2") (pinfunction "CS_2") (pintype "bidirectional"))
      (node (ref "V2") (pin "11") (pinfunction "Y_11") (pintype "tri_state"))
    )
    (net (code "97") (name "/~{SS2}") (class "Default")
      (node (ref "IC1") (pin "14") (pinfunction "RG9_14") (pintype "bidirectional"))
      (node (ref "V2") (pin "12") (pinfunction "A_12") (pintype "input"))
    )
    (net (code "98") (name "Net-(IC1-VDDCORE)") (class "Default")
      (node (ref "C7") (pin "1") (pinfunction "1_1") (pintype "passive"))
      (node (ref "IC1") (pin "85") (pinfunction "VDDCORE_85") (pintype "power_in"))
    )
    (net (code "99") (name "Net-(U1-DIN)") (class "Default")
      (node (ref "R5") (pin "2") (pinfunction "2_2") (pintype "passive"))
      (node (ref "U1") (pin "10") (pinfunction "DIN_10") (pintype "bidirectional"))
    )
    (net (code "100") (name "Net-(U1-DOUT{slash}DRDY)") (class "Default")
      (node (ref "R6") (pin "2") (pinfunction "2_2") (pintype "passive"))
      (node (ref "U1") (pin "9") (pinfunction "DOUT/DRDY_9") (pintype "bidirectional"))
    )
    (net (code "101") (name "Net-(U1-SCLK)") (class "Default")
      (node (ref "R11") (pin "1") (pinfunction "1_1") (pintype "passive"))
      (node (ref "U1") (pin "1") (pinfunction "SCLK_1") (pintype "bidirectional"))
    )
    (net (code "102") (name "Net-(U2-DIN)") (class "Default")
      (node (ref "R12") (pin "2") (pinfunction "2_2") (pintype "passive"))
      (node (ref "U2") (pin "10") (pinfunction "DIN_10") (pintype "bidirectional"))
    )
    (net (code "103") (name "Net-(U2-DOUT{slash}DRDY)") (class "Default")
      (node (ref "R13") (pin "2") (pinfunction "2_2") (pintype "passive"))
      (node (ref "U2") (pin "9") (pinfunction "DOUT/DRDY_9") (pintype "bidirectional"))
    )
    (net (code "104") (name "Net-(U2-SCLK)") (class "Default")
      (node (ref "R14") (pin "1") (pinfunction "1_1") (pintype "passive"))
      (node (ref "U2") (pin "1") (pinfunction "SCLK_1") (pintype "bidirectional"))
    )
    (net (code "105") (name "unconnected-(IC1-RA2-Pad58)") (class "Default")
      (node (ref "IC1") (pin "58") (pinfunction "RA2_58") (pintype "bidirectional"))
    )
    (net (code "106") (name "unconnected-(IC1-RA3-Pad59)") (class "Default")
      (node (ref "IC1") (pin "59") (pinfunction "RA3_59") (pintype "bidirectional"))
    )
    (net (code "107") (name "unconnected-(IC1-RA6-Pad91)") (class "Default")
      (node (ref "IC1") (pin "91") (pinfunction "RA6_91") (pintype "bidirectional"))
    )
    (net (code "108") (name "unconnected-(IC1-RA7-Pad92)") (class "Default")
      (node (ref "IC1") (pin "92") (pinfunction "RA7_92") (pintype "bidirectional"))
    )
    (net (code "109") (name "unconnected-(IC1-RA9-Pad28)") (class "Default")
      (node (ref "IC1") (pin "28") (pinfunction "RA9_28") (pintype "bidirectional"))
    )
    (net (code "110") (name "unconnected-(IC1-RA10-Pad29)") (class "Default")
      (node (ref "IC1") (pin "29") (pinfunction "RA10_29") (pintype "bidirectional"))
    )
    (net (code "111") (name "unconnected-(IC1-RA14-Pad66)") (class "Default")
      (node (ref "IC1") (pin "66") (pinfunction "RA14_66") (pintype "bidirectional"))
    )
    (net (code "112") (name "unconnected-(IC1-RA15-Pad67)") (class "Default")
      (node (ref "IC1") (pin "67") (pinfunction "RA15_67") (pintype "bidirectional"))
    )
    (net (code "113") (name "unconnected-(IC1-RB14-Pad43)") (class "Default")
      (node (ref "IC1") (pin "43") (pinfunction "RB14_43") (pintype "bidirectional"))
    )
    (net (code "114") (name "unconnected-(IC1-RB15-Pad44)") (class "Default")
      (node (ref "IC1") (pin "44") (pinfunction "RB15_44") (pintype "bidirectional"))
    )
    (net (code "115") (name "unconnected-(IC1-RC13-Pad73)") (class "Default")
      (node (ref "IC1") (pin "73") (pinfunction "RC13_73") (pintype "bidirectional"))
    )
    (net (code "116") (name "unconnected-(IC1-RC14-Pad74)") (class "Default")
      (node (ref "IC1") (pin "74") (pinfunction "RC14_74") (pintype "bidirectional"))
    )
    (net (code "117") (name "unconnected-(IC1-RD10-Pad70)") (class "Default")
      (node (ref "IC1") (pin "70") (pinfunction "RD10_70") (pintype "bidirectional"))
    )
    (net (code "118") (name "unconnected-(IC1-RD11-Pad71)") (class "Default")
      (node (ref "IC1") (pin "71") (pinfunction "RD11_71") (pintype "bidirectional"))
    )
    (net (code "119") (name "unconnected-(IC1-RD12-Pad79)") (class "Default")
      (node (ref "IC1") (pin "79") (pinfunction "RD12_79") (pintype "bidirectional"))
    )
    (net (code "120") (name "unconnected-(IC1-RD13-Pad80)") (class "Default")
      (node (ref "IC1") (pin "80") (pinfunction "RD13_80") (pintype "bidirectional"))
    )
    (net (code "121") (name "unconnected-(IC1-RD15-Pad48)") (class "Default")
      (node (ref "IC1") (pin "48") (pinfunction "RD15_48") (pintype "bidirectional"))
    )
    (net (code "122") (name "unconnected-(IC1-RF0-Pad87)") (class "Default")
      (node (ref "IC1") (pin "87") (pinfunction "RF0_87") (pintype "bidirectional"))
    )
    (net (code "123") (name "unconnected-(IC1-RF1-Pad88)") (class "Default")
      (node (ref "IC1") (pin "88") (pinfunction "RF1_88") (pintype "bidirectional"))
    )
    (net (code "124") (name "unconnected-(IC1-RF12-Pad40)") (class "Default")
      (node (ref "IC1") (pin "40") (pinfunction "RF12_40") (pintype "bidirectional"))
    )
    (net (code "125") (name "unconnected-(IC1-RF13-Pad39)") (class "Default")
      (node (ref "IC1") (pin "39") (pinfunction "RF13_39") (pintype "bidirectional"))
    )
    (net (code "126") (name "unconnected-(IC1-RG0-Pad90)") (class "Default")
      (node (ref "IC1") (pin "90") (pinfunction "RG0_90") (pintype "bidirectional"))
    )
    (net (code "127") (name "unconnected-(IC1-RG1-Pad89)") (class "Default")
      (node (ref "IC1") (pin "89") (pinfunction "RG1_89") (pintype "bidirectional"))
    )
    (net (code "128") (name "unconnected-(IC1-RG12-Pad96)") (class "Default")
      (node (ref "IC1") (pin "96") (pinfunction "RG12_96") (pintype "bidirectional"))
    )
    (net (code "129") (name "unconnected-(IC1-RG13-Pad97)") (class "Default")
      (node (ref "IC1") (pin "97") (pinfunction "RG13_97") (pintype "bidirectional"))
    )
    (net (code "130") (name "unconnected-(IC1-RG14-Pad95)") (class "Default")
      (node (ref "IC1") (pin "95") (pinfunction "RG14_95") (pintype "bidirectional"))
    )
    (net (code "131") (name "unconnected-(IC1-TCK-Pad38)") (class "Default")
      (node (ref "IC1") (pin "38") (pinfunction "TCK_38") (pintype "input"))
    )
    (net (code "132") (name "unconnected-(IC1-TDI-Pad60)") (class "Default")
      (node (ref "IC1") (pin "60") (pinfunction "TDI_60") (pintype "input"))
    )
    (net (code "133") (name "unconnected-(IC1-TDO-Pad61)") (class "Default")
      (node (ref "IC1") (pin "61") (pinfunction "TDO_61") (pintype "output"))
    )
    (net (code "134") (name "unconnected-(J2-PadA1)") (class "Default")
      (node (ref "J2") (pin "A1") (pinfunction "A1_A1") (pintype "passive"))
    )
    (net (code "135") (name "unconnected-(J2-PadA2)") (class "Default")
      (node (ref "J2") (pin "A2") (pinfunction "A2_A2") (pintype "passive"))
    )
    (net (code "136") (name "unconnected-(J2-PadA10)") (class "Default")
      (node (ref "J2") (pin "A10") (pinfunction "A10_A10") (pintype "passive"))
    )
    (net (code "137") (name "unconnected-(J2-PadA15)") (class "Default")
      (node (ref "J2") (pin "A15") (pinfunction "A15_A15") (pintype "passive"))
    )
    (net (code "138") (name "unconnected-(J2-PadA16)") (class "Default")
      (node (ref "J2") (pin "A16") (pinfunction "A16_A16") (pintype "passive"))
    )
    (net (code "139") (name "unconnected-(J2-PadA17)") (class "Default")
      (node (ref "J2") (pin "A17") (pinfunction "A17_A17") (pintype "passive"))
    )
    (net (code "140") (name "unconnected-(J2-PadA18)") (class "Default")
      (node (ref "J2") (pin "A18") (pinfunction "A18_A18") (pintype "passive"))
    )
    (net (code "141") (name "unconnected-(J2-PadA19)") (class "Default")
      (node (ref "J2") (pin "A19") (pinfunction "A19_A19") (pintype "passive"))
    )
    (net (code "142") (name "unconnected-(J2-PadA20)") (class "Default")
      (node (ref "J2") (pin "A20") (pinfunction "A20_A20") (pintype "passive"))
    )
    (net (code "143") (name "unconnected-(J2-PadA21)") (class "Default")
      (node (ref "J2") (pin "A21") (pinfunction "A21_A21") (pintype "passive"))
    )
    (net (code "144") (name "unconnected-(J2-PadA22)") (class "Default")
      (node (ref "J2") (pin "A22") (pinfunction "A22_A22") (pintype "passive"))
    )
    (net (code "145") (name "unconnected-(J2-PadA23)") (class "Default")
      (node (ref "J2") (pin "A23") (pinfunction "A23_A23") (pintype "passive"))
    )
    (net (code "146") (name "unconnected-(J2-PadA24)") (class "Default")
      (node (ref "J2") (pin "A24") (pinfunction "A24_A24") (pintype "passive"))
    )
    (net (code "147") (name "unconnected-(J2-PadA25)") (class "Default")
      (node (ref "J2") (pin "A25") (pinfunction "A25_A25") (pintype "passive"))
    )
    (net (code "148") (name "unconnected-(J2-PadA26)") (class "Default")
      (node (ref "J2") (pin "A26") (pinfunction "A26_A26") (pintype "passive"))
    )
    (net (code "149") (name "unconnected-(J2-PadA27)") (class "Default")
      (node (ref "J2") (pin "A27") (pinfunction "A27_A27") (pintype "passive"))
    )
    (net (code "150") (name "unconnected-(J2-PadA28)") (class "Default")
      (node (ref "J2") (pin "A28") (pinfunction "A28_A28") (pintype "passive"))
    )
    (net (code "151") (name "unconnected-(J2-PadA29)") (class "Default")
      (node (ref "J2") (pin "A29") (pinfunction "A29_A29") (pintype "passive"))
    )
    (net (code "152") (name "unconnected-(J2-PadA30)") (class "Default")
      (node (ref "J2") (pin "A30") (pinfunction "A30_A30") (pintype "passive"))
    )
    (net (code "153") (name "unconnected-(J2-PadA31)") (class "Default")
      (node (ref "J2") (pin "A31") (pinfunction "A31_A31") (pintype "passive"))
    )
    (net (code "154") (name "unconnected-(J2-PadA32)") (class "Default")
      (node (ref "J2") (pin "A32") (pinfunction "A32_A32") (pintype "passive"))
    )
    (net (code "155") (name "unconnected-(J2-PadB10)") (class "Default")
      (node (ref "J2") (pin "B10") (pinfunction "B10_B10") (pintype "passive"))
    )
    (net (code "156") (name "unconnected-(J2-PadB15)") (class "Default")
      (node (ref "J2") (pin "B15") (pinfunction "B15_B15") (pintype "passive"))
    )
    (net (code "157") (name "unconnected-(J2-PadB16)") (class "Default")
      (node (ref "J2") (pin "B16") (pinfunction "B16_B16") (pintype "passive"))
    )
    (net (code "158") (name "unconnected-(J2-PadB17)") (class "Default")
      (node (ref "J2") (pin "B17") (pinfunction "B17_B17") (pintype "passive"))
    )
    (net (code "159") (name "unconnected-(J2-PadB18)") (class "Default")
      (node (ref "J2") (pin "B18") (pinfunction "B18_B18") (pintype "passive"))
    )
    (net (code "160") (name "unconnected-(J2-PadB19)") (class "Default")
      (node (ref "J2") (pin "B19") (pinfunction "B19_B19") (pintype "passive"))
    )
    (net (code "161") (name "unconnected-(J2-PadB20)") (class "Default")
      (node (ref "J2") (pin "B20") (pinfunction "B20_B20") (pintype "passive"))
    )
    (net (code "162") (name "unconnected-(J2-PadB21)") (class "Default")
      (node (ref "J2") (pin "B21") (pinfunction "B21_B21") (pintype "passive"))
    )
    (net (code "163") (name "unconnected-(J2-PadB22)") (class "Default")
      (node (ref "J2") (pin "B22") (pinfunction "B22_B22") (pintype "passive"))
    )
    (net (code "164") (name "unconnected-(J2-PadB23)") (class "Default")
      (node (ref "J2") (pin "B23") (pinfunction "B23_B23") (pintype "passive"))
    )
    (net (code "165") (name "unconnected-(J2-PadB24)") (class "Default")
      (node (ref "J2") (pin "B24") (pinfunction "B24_B24") (pintype "passive"))
    )
    (net (code "166") (name "unconnected-(J2-PadB25)") (class "Default")
      (node (ref "J2") (pin "B25") (pinfunction "B25_B25") (pintype "passive"))
    )
    (net (code "167") (name "unconnected-(J2-PadB26)") (class "Default")
      (node (ref "J2") (pin "B26") (pinfunction "B26_B26") (pintype "passive"))
    )
    (net (code "168") (name "unconnected-(J2-PadB27)") (class "Default")
      (node (ref "J2") (pin "B27") (pinfunction "B27_B27") (pintype "passive"))
    )
    (net (code "169") (name "unconnected-(J2-PadB28)") (class "Default")
      (node (ref "J2") (pin "B28") (pinfunction "B28_B28") (pintype "passive"))
    )
    (net (code "170") (name "unconnected-(J2-PadB29)") (class "Default")
      (node (ref "J2") (pin "B29") (pinfunction "B29_B29") (pintype "passive"))
    )
    (net (code "171") (name "unconnected-(J2-PadB30)") (class "Default")
      (node (ref "J2") (pin "B30") (pinfunction "B30_B30") (pintype "passive"))
    )
    (net (code "172") (name "unconnected-(J2-PadB31)") (class "Default")
      (node (ref "J2") (pin "B31") (pinfunction "B31_B31") (pintype "passive"))
    )
    (net (code "173") (name "unconnected-(J2-PadB32)") (class "Default")
      (node (ref "J2") (pin "B32") (pinfunction "B32_B32") (pintype "passive"))
    )
    (net (code "174") (name "unconnected-(J2-PadC10)") (class "Default")
      (node (ref "J2") (pin "C10") (pinfunction "C10_C10") (pintype "passive"))
    )
    (net (code "175") (name "unconnected-(J2-PadC15)") (class "Default")
      (node (ref "J2") (pin "C15") (pinfunction "C15_C15") (pintype "passive"))
    )
    (net (code "176") (name "unconnected-(J2-PadC16)") (class "Default")
      (node (ref "J2") (pin "C16") (pinfunction "C16_C16") (pintype "passive"))
    )
    (net (code "177") (name "unconnected-(J2-PadC17)") (class "Default")
      (node (ref "J2") (pin "C17") (pinfunction "C17_C17") (pintype "passive"))
    )
    (net (code "178") (name "unconnected-(J2-PadC18)") (class "Default")
      (node (ref "J2") (pin "C18") (pinfunction "C18_C18") (pintype "passive"))
    )
    (net (code "179") (name "unconnected-(J2-PadC19)") (class "Default")
      (node (ref "J2") (pin "C19") (pinfunction "C19_C19") (pintype "passive"))
    )
    (net (code "180") (name "unconnected-(J2-PadC20)") (class "Default")
      (node (ref "J2") (pin "C20") (pinfunction "C20_C20") (pintype "passive"))
    )
    (net (code "181") (name "unconnected-(J2-PadC21)") (class "Default")
      (node (ref "J2") (pin "C21") (pinfunction "C21_C21") (pintype "passive"))
    )
    (net (code "182") (name "unconnected-(J2-PadC22)") (class "Default")
      (node (ref "J2") (pin "C22") (pinfunction "C22_C22") (pintype "passive"))
    )
    (net (code "183") (name "unconnected-(J2-PadC23)") (class "Default")
      (node (ref "J2") (pin "C23") (pinfunction "C23_C23") (pintype "passive"))
    )
    (net (code "184") (name "unconnected-(J2-PadC24)") (class "Default")
      (node (ref "J2") (pin "C24") (pinfunction "C24_C24") (pintype "passive"))
    )
    (net (code "185") (name "unconnected-(J2-PadC25)") (class "Default")
      (node (ref "J2") (pin "C25") (pinfunction "C25_C25") (pintype "passive"))
    )
    (net (code "186") (name "unconnected-(J2-PadC26)") (class "Default")
      (node (ref "J2") (pin "C26") (pinfunction "C26_C26") (pintype "passive"))
    )
    (net (code "187") (name "unconnected-(J2-PadC27)") (class "Default")
      (node (ref "J2") (pin "C27") (pinfunction "C27_C27") (pintype "passive"))
    )
    (net (code "188") (name "unconnected-(J2-PadC28)") (class "Default")
      (node (ref "J2") (pin "C28") (pinfunction "C28_C28") (pintype "passive"))
    )
    (net (code "189") (name "unconnected-(J2-PadC29)") (class "Default")
      (node (ref "J2") (pin "C29") (pinfunction "C29_C29") (pintype "passive"))
    )
    (net (code "190") (name "unconnected-(J2-PadC30)") (class "Default")
      (node (ref "J2") (pin "C30") (pinfunction "C30_C30") (pintype "passive"))
    )
    (net (code "191") (name "unconnected-(J2-PadC31)") (class "Default")
      (node (ref "J2") (pin "C31") (pinfunction "C31_C31") (pintype "passive"))
    )
    (net (code "192") (name "unconnected-(J2-PadC32)") (class "Default")
      (node (ref "J2") (pin "C32") (pinfunction "C32_C32") (pintype "passive"))
    )
    (net (code "193") (name "unconnected-(JP1-Pad6)") (class "Default")
      (node (ref "JP1") (pin "6") (pinfunction "6_6") (pintype "passive"))
    )
    (net (code "194") (name "unconnected-(JP2-Pad6)") (class "Default")
      (node (ref "JP2") (pin "6") (pinfunction "6_6") (pintype "passive"))
    )
    (net (code "195") (name "unconnected-(PIC16-Pad2)") (class "Default")
      (node (ref "PIC16") (pin "2") (pinfunction "2_2") (pintype "passive"))
    )
    (net (code "196") (name "unconnected-(PIC16-Pad3)") (class "Default")
      (node (ref "PIC16") (pin "3") (pinfunction "3_3") (pintype "passive"))
    )
    (net (code "197") (name "unconnected-(PIC16-Pad13)") (class "Default")
      (node (ref "PIC16") (pin "13") (pinfunction "13_13") (pintype "passive"))
    )
    (net (code "198") (name "unconnected-(U$1-CLK-Pad6)") (class "Default")
      (node (ref "U$1") (pin "6") (pinfunction "CLK_6") (pintype "bidirectional"))
    )
    (net (code "199") (name "unconnected-(U$1-CS-Pad5)") (class "Default")
      (node (ref "U$1") (pin "5") (pinfunction "CS_5") (pintype "bidirectional"))
    )
    (net (code "200") (name "unconnected-(U$1-GND2-Pad15)") (class "Default")
      (node (ref "U$1") (pin "15") (pinfunction "GND2_15") (pintype "bidirectional"))
    )
    (net (code "201") (name "unconnected-(U$1-MISO-Pad7)") (class "Default")
      (node (ref "U$1") (pin "7") (pinfunction "MISO_7") (pintype "bidirectional"))
    )
    (net (code "202") (name "unconnected-(U$1-MOSI-Pad8)") (class "Default")
      (node (ref "U$1") (pin "8") (pinfunction "MOSI_8") (pintype "bidirectional"))
    )
    (net (code "203") (name "unconnected-(U$1-NAV-Pad14)") (class "Default")
      (node (ref "U$1") (pin "14") (pinfunction "NAV_14") (pintype "bidirectional"))
    )
    (net (code "204") (name "unconnected-(U$1-RX1-Pad12)") (class "Default")
      (node (ref "U$1") (pin "12") (pinfunction "RX1_12") (pintype "bidirectional"))
    )
    (net (code "205") (name "unconnected-(U$1-SCL-Pad10)") (class "Default")
      (node (ref "U$1") (pin "10") (pinfunction "SCL_10") (pintype "bidirectional"))
    )
    (net (code "206") (name "unconnected-(U$1-SDA-Pad9)") (class "Default")
      (node (ref "U$1") (pin "9") (pinfunction "SDA_9") (pintype "bidirectional"))
    )
    (net (code "207") (name "unconnected-(U$1-TX1-Pad11)") (class "Default")
      (node (ref "U$1") (pin "11") (pinfunction "TX1_11") (pintype "bidirectional"))
    )
    (net (code "208") (name "unconnected-(X1-Pad15)") (class "Default")
      (node (ref "X1") (pin "15") (pinfunction "15_15") (pintype "passive"))
    )
    (net (code "209") (name "unconnected-(X2-Pad3)") (class "Default")
      (node (ref "X2") (pin "3") (pinfunction "3_3") (pintype "passive"))
    )
    (net (code "210") (name "unconnected-(X2-Pad10)") (class "Default")
      (node (ref "X2") (pin "10") (pinfunction "10_10") (pintype "passive"))
    )
    (net (code "211") (name "unconnected-(X2-Pad11)") (class "Default")
      (node (ref "X2") (pin "11") (pinfunction "11_11") (pintype "passive"))
    )
  )
)
